# MAZ000160_-_Diagrama_el_ctrico.net
KiCad netlist of a schematic drawn in Altium Designer
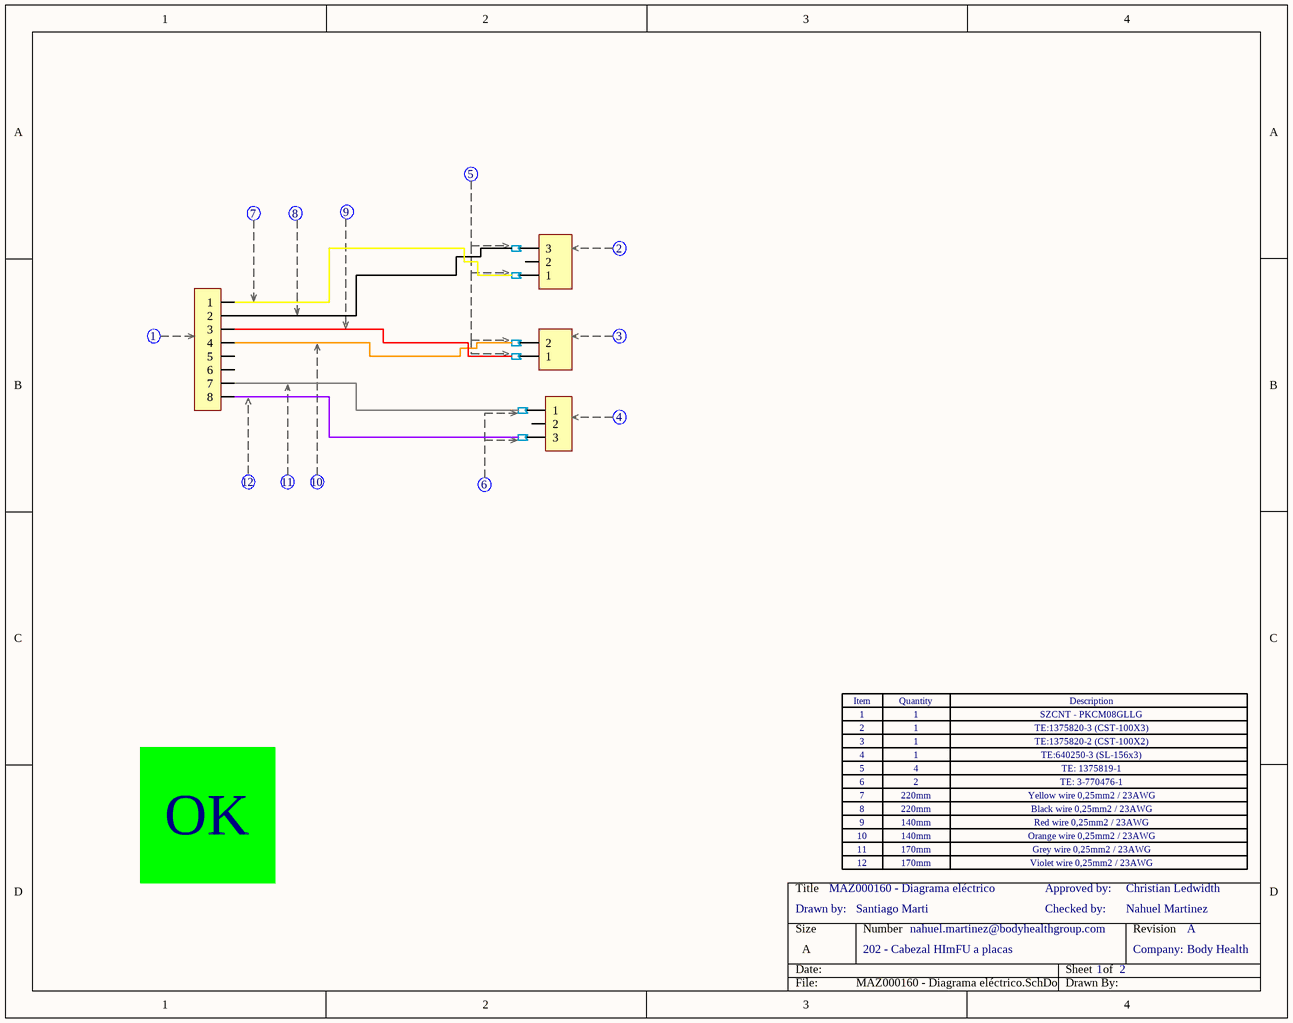
[diagram p0: MAZ000160 - Diagrama eléctrico.SchDoc]

(export (version "E")
  (design (tool "Eeschema 10.0.6"))
  (components
    (comp (ref "Con1")
      (value "CST-100-3")
      (description "CONN RCPT HSNG 3POS CST-100 II")
      (libsource (lib "LibreriaParaPlanos") (part "CST-100-3"))
    )
    (comp (ref "Con2")
      (value "CST-100-2")
      (description "CONN RCPT HSNG 2POS CST-100 II")
      (libsource (lib "LibreriaParaPlanos") (part "CST-100-2"))
    )
    (comp (ref "Con3")
      (value "SL156-3")
      (description "CONN RECEPT 3 POS W/RAMP SL-156")
      (libsource (lib "LibreriaParaPlanos") (part "SL156-3"))
    )
    (comp (ref "Conn1")
      (value "SZCNT_08_Hembra")
      (description "Conector SZCNT 8 vías hembra para gabinete")
      (libsource (lib "LibreriaParaPlanos") (part "SZCNT_08_Hembra"))
    )
    (comp (ref "Soc1")
      (value "sock_CST_1375819-1")
      (description "CONN SOCKET 22-26AWG CRIMP TIN")
      (libsource (lib "LibreriaParaPlanos") (part "sock_CST_1375819-1"))
    )
    (comp (ref "Soc2")
      (value "sock_SL156_770476-1")
      (description "CONN SOCKET 18-24AWG CRIMP TIN")
      (libsource (lib "LibreriaParaPlanos") (part "sock_SL156_770476-1"))
    )
    (comp (ref "Soc3")
      (value "sock_SL156_770476-1")
      (description "CONN SOCKET 18-24AWG CRIMP TIN")
      (libsource (lib "LibreriaParaPlanos") (part "sock_SL156_770476-1"))
    )
    (comp (ref "Soc4")
      (value "sock_SL156_770476-1")
      (description "CONN SOCKET 18-24AWG CRIMP TIN")
      (libsource (lib "LibreriaParaPlanos") (part "sock_SL156_770476-1"))
    )
    (comp (ref "Soc5")
      (value "sock_CST_1375819-1")
      (description "CONN SOCKET 22-26AWG CRIMP TIN")
      (libsource (lib "LibreriaParaPlanos") (part "sock_CST_1375819-1"))
    )
    (comp (ref "Soc6")
      (value "sock_CST_1375819-1")
      (description "CONN SOCKET 22-26AWG CRIMP TIN")
      (libsource (lib "LibreriaParaPlanos") (part "sock_CST_1375819-1"))
    )
    (comp (ref "Soc7")
      (value "sock_CST_1375819-1")
      (description "CONN SOCKET 22-26AWG CRIMP TIN")
      (libsource (lib "LibreriaParaPlanos") (part "sock_CST_1375819-1"))
    )
    (comp (ref "Soc8")
      (value "sock_SL156_770476-1")
      (description "CONN SOCKET 18-24AWG CRIMP TIN")
      (libsource (lib "LibreriaParaPlanos") (part "sock_SL156_770476-1"))
    )
    (comp (ref "Soc9")
      (value "sock_SL156_770476-1")
      (description "CONN SOCKET 18-24AWG CRIMP TIN")
      (libsource (lib "LibreriaParaPlanos") (part "sock_SL156_770476-1"))
    )
    (comp (ref "Soc10")
      (value "sock_SL156_770476-1")
      (description "CONN SOCKET 18-24AWG CRIMP TIN")
      (libsource (lib "LibreriaParaPlanos") (part "sock_SL156_770476-1"))
    )
    (comp (ref "Soc11")
      (value "sock_SL156_770476-1")
      (description "CONN SOCKET 18-24AWG CRIMP TIN")
      (libsource (lib "LibreriaParaPlanos") (part "sock_SL156_770476-1"))
    )
    (comp (ref "Zoc1")
      (value "Zócalo_Header")
      (description "Header para el zócalo de referencias")
      (libsource (lib "LibreriaParaPlanos") (part "Zócalo_Header"))
    )
    (comp (ref "Zoc2")
      (value "Zócalo_Item")
      (description "Ítem para el zócalo de referencias")
      (libsource (lib "LibreriaParaPlanos") (part "Zócalo_Item"))
    )
    (comp (ref "Zoc3")
      (value "Zócalo_Item")
      (description "Ítem para el zócalo de referencias")
      (libsource (lib "LibreriaParaPlanos") (part "Zócalo_Item"))
    )
    (comp (ref "Zoc4")
      (value "Zócalo_Item")
      (description "Ítem para el zócalo de referencias")
      (libsource (lib "LibreriaParaPlanos") (part "Zócalo_Item"))
    )
    (comp (ref "Zoc5")
      (value "Zócalo_Item")
      (description "Ítem para el zócalo de referencias")
      (libsource (lib "LibreriaParaPlanos") (part "Zócalo_Item"))
    )
    (comp (ref "Zoc6")
      (value "Zócalo_Item")
      (description "Ítem para el zócalo de referencias")
      (libsource (lib "LibreriaParaPlanos") (part "Zócalo_Item"))
    )
    (comp (ref "Zoc7")
      (value "Zócalo_Item")
      (description "Ítem para el zócalo de referencias")
      (libsource (lib "LibreriaParaPlanos") (part "Zócalo_Item"))
    )
    (comp (ref "Zoc8")
      (value "Zócalo_Item")
      (description "Ítem para el zócalo de referencias")
      (libsource (lib "LibreriaParaPlanos") (part "Zócalo_Item"))
    )
    (comp (ref "Zoc9")
      (value "Zócalo_Item")
      (description "Ítem para el zócalo de referencias")
      (libsource (lib "LibreriaParaPlanos") (part "Zócalo_Item"))
    )
    (comp (ref "Zoc10")
      (value "Zócalo_Item")
      (description "Ítem para el zócalo de referencias")
      (libsource (lib "LibreriaParaPlanos") (part "Zócalo_Item"))
    )
    (comp (ref "Zoc11")
      (value "Zócalo_Item")
      (description "Ítem para el zócalo de referencias")
      (libsource (lib "LibreriaParaPlanos") (part "Zócalo_Item"))
    )
    (comp (ref "Zoc12")
      (value "Zócalo_Item")
      (description "Ítem para el zócalo de referencias")
      (libsource (lib "LibreriaParaPlanos") (part "Zócalo_Item"))
    )
    (comp (ref "Zoc13")
      (value "Zócalo_Item")
      (description "Ítem para el zócalo de referencias")
      (libsource (lib "LibreriaParaPlanos") (part "Zócalo_Item"))
    )
  )
  (nets
    (net (code "1") (name "Net-(Con1-Pad1)") (class "Default")
      (node (ref "Con1") (pin "1") (pinfunction "1_1") (pintype "passive"))
      (node (ref "Soc5") (pin "0") (pinfunction "0_0") (pintype "passive"))
    )
    (net (code "2") (name "Net-(Con1-Pad3)") (class "Default")
      (node (ref "Con1") (pin "3") (pinfunction "3_3") (pintype "passive"))
      (node (ref "Soc1") (pin "0") (pinfunction "0_0") (pintype "passive"))
    )
    (net (code "3") (name "Net-(Con2-Pad1)") (class "Default")
      (node (ref "Con2") (pin "1") (pinfunction "1_1") (pintype "passive"))
      (node (ref "Soc7") (pin "0") (pinfunction "0_0") (pintype "passive"))
    )
    (net (code "4") (name "Net-(Con2-Pad2)") (class "Default")
      (node (ref "Con2") (pin "2") (pinfunction "2_2") (pintype "passive"))
      (node (ref "Soc6") (pin "0") (pinfunction "0_0") (pintype "passive"))
    )
    (net (code "5") (name "Net-(Con3-Pad1)") (class "Default")
      (node (ref "Con3") (pin "1") (pinfunction "1_1") (pintype "passive"))
      (node (ref "Soc2") (pin "0") (pinfunction "0_0") (pintype "passive"))
    )
    (net (code "6") (name "Net-(Con3-Pad3)") (class "Default")
      (node (ref "Con3") (pin "3") (pinfunction "3_3") (pintype "passive"))
      (node (ref "Soc3") (pin "0") (pinfunction "0_0") (pintype "passive"))
    )
    (net (code "7") (name "Net-(Conn1-Pad1)") (class "Default")
      (node (ref "Conn1") (pin "1") (pinfunction "1_1") (pintype "passive"))
      (node (ref "Soc5") (pin "1") (pinfunction "1_1") (pintype "passive"))
    )
    (net (code "8") (name "Net-(Conn1-Pad2)") (class "Default")
      (node (ref "Conn1") (pin "2") (pinfunction "2_2") (pintype "passive"))
      (node (ref "Soc1") (pin "1") (pinfunction "1_1") (pintype "passive"))
    )
    (net (code "9") (name "Net-(Conn1-Pad3)") (class "Default")
      (node (ref "Conn1") (pin "3") (pinfunction "3_3") (pintype "passive"))
      (node (ref "Soc7") (pin "1") (pinfunction "1_1") (pintype "passive"))
    )
    (net (code "10") (name "Net-(Conn1-Pad4)") (class "Default")
      (node (ref "Conn1") (pin "4") (pinfunction "4_4") (pintype "passive"))
      (node (ref "Soc6") (pin "1") (pinfunction "1_1") (pintype "passive"))
    )
    (net (code "11") (name "Net-(Conn1-Pad7)") (class "Default")
      (node (ref "Conn1") (pin "7") (pinfunction "7_7") (pintype "passive"))
      (node (ref "Soc2") (pin "1") (pinfunction "1_1") (pintype "passive"))
    )
    (net (code "12") (name "Net-(Conn1-Pad8)") (class "Default")
      (node (ref "Conn1") (pin "8") (pinfunction "8_8") (pintype "passive"))
      (node (ref "Soc3") (pin "1") (pinfunction "1_1") (pintype "passive"))
    )
    (net (code "13") (name "unconnected-(Con1-Pad2)") (class "Default")
      (node (ref "Con1") (pin "2") (pinfunction "2_2") (pintype "passive"))
    )
    (net (code "14") (name "unconnected-(Con3-Pad2)") (class "Default")
      (node (ref "Con3") (pin "2") (pinfunction "2_2") (pintype "passive"))
    )
    (net (code "15") (name "unconnected-(Conn1-Pad5)") (class "Default")
      (node (ref "Conn1") (pin "5") (pinfunction "5_5") (pintype "passive"))
    )
    (net (code "16") (name "unconnected-(Conn1-Pad6)") (class "Default")
      (node (ref "Conn1") (pin "6") (pinfunction "6_6") (pintype "passive"))
    )
  )
)
